# LoraWAN_Node.net
KiCad netlist of a schematic drawn in Altium Designer
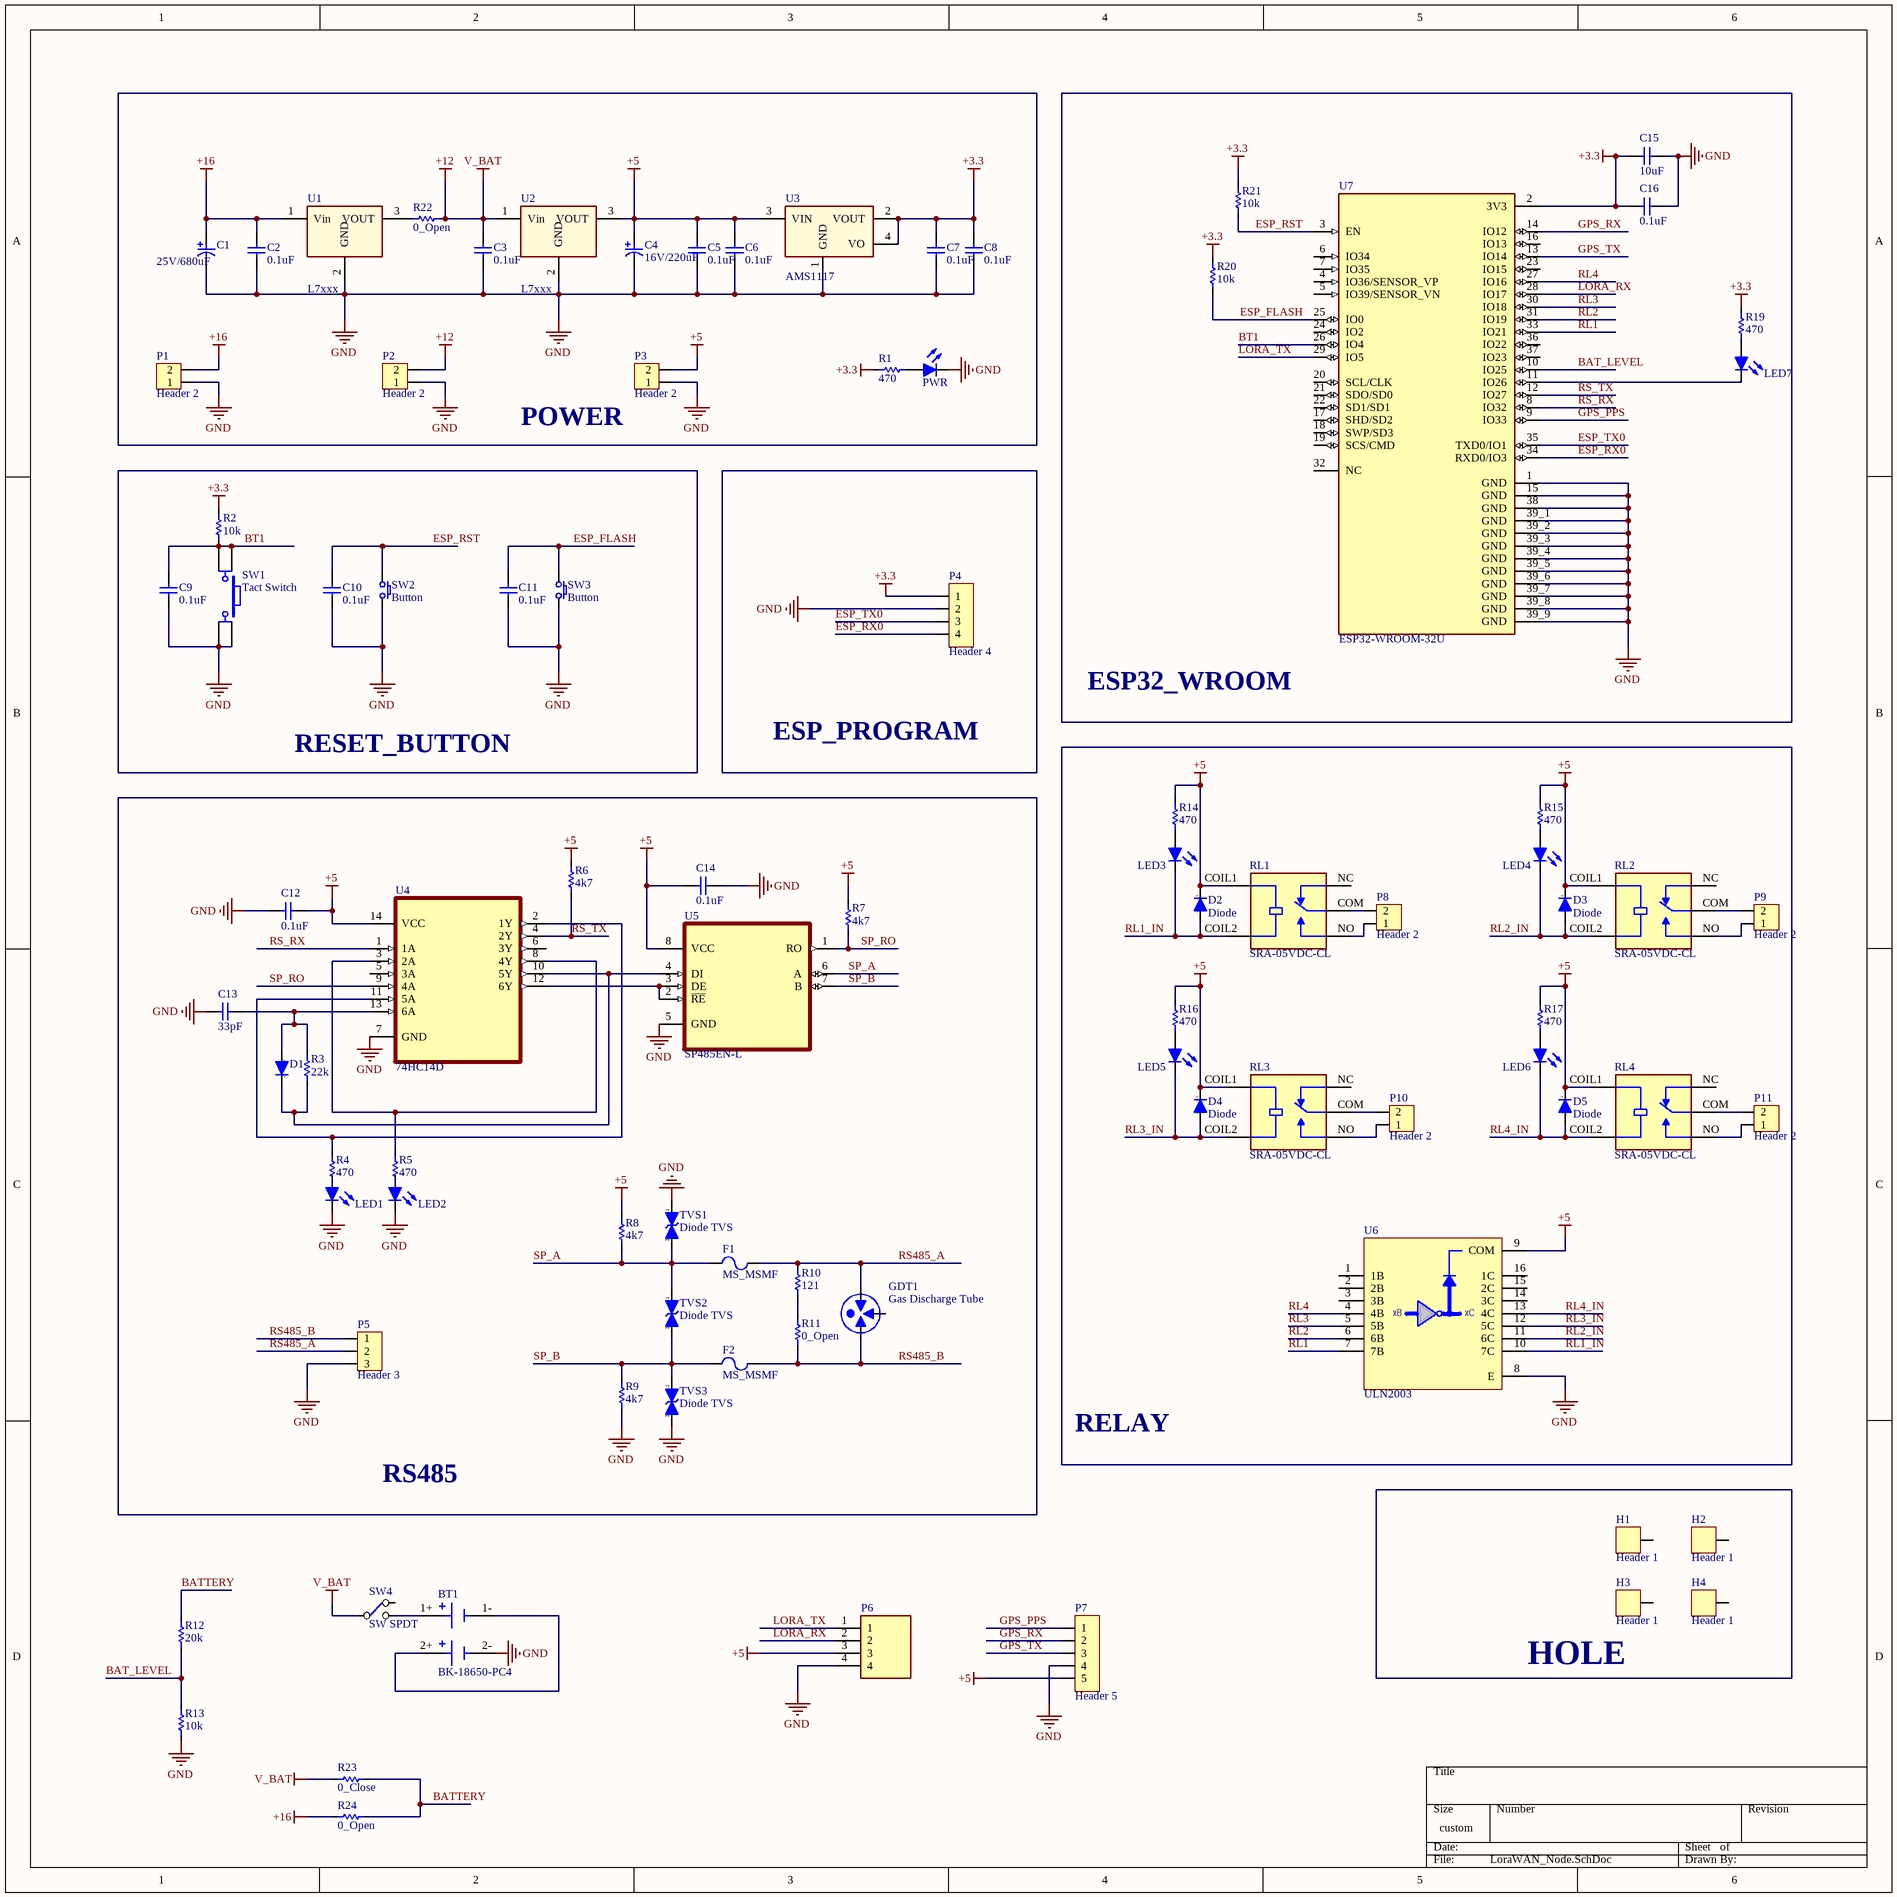
[diagram p0: LoraWAN_Node.SchDoc]

(export (version "E")
  (design (tool "Eeschema 10.0.6"))
  (components
    (comp (ref "BT1")
      (value "BK-18650-PC4")
      (footprint "BAT_BK-18650-PC4")
      (description "Battery Holder (Open) 18650 2 Cell PC Pin")
      (libsource (lib "BK-18650-PC4") (part "BK-18650-PC4"))
    )
    (comp (ref "C1")
      (value "25V/680uF")
      (footprint "C SMD ALU (G)")
      (description "Capacitor pol")
      (libsource (lib "BKIT4U_LIB_NEW") (part "Capacitor"))
    )
    (comp (ref "C2")
      (value "0.1uF")
      (footprint "C 0603 (1608)")
      (description "Capacitor non-pol")
      (libsource (lib "BKIT4U_LIB_NEW") (part "Capacitor NP"))
    )
    (comp (ref "C3")
      (value "0.1uF")
      (footprint "C 0603 (1608)")
      (description "Capacitor non-pol")
      (libsource (lib "BKIT4U_LIB_NEW") (part "Capacitor NP"))
    )
    (comp (ref "C4")
      (value "16V/220uF")
      (footprint "C SMD ALU (D8)")
      (description "Capacitor pol")
      (libsource (lib "BKIT4U_LIB_NEW") (part "Capacitor"))
    )
    (comp (ref "C5")
      (value "0.1uF")
      (footprint "C 0603 (1608)")
      (description "Capacitor non-pol")
      (libsource (lib "BKIT4U_LIB_NEW") (part "Capacitor NP"))
    )
    (comp (ref "C6")
      (value "0.1uF")
      (footprint "C 0603 (1608)")
      (description "Capacitor non-pol")
      (libsource (lib "BKIT4U_LIB_NEW") (part "Capacitor NP"))
    )
    (comp (ref "C7")
      (value "0.1uF")
      (footprint "C 0603 (1608)")
      (description "Capacitor non-pol")
      (libsource (lib "BKIT4U_LIB_NEW") (part "Capacitor NP"))
    )
    (comp (ref "C8")
      (value "0.1uF")
      (footprint "C 0603 (1608)")
      (description "Capacitor non-pol")
      (libsource (lib "BKIT4U_LIB_NEW") (part "Capacitor NP"))
    )
    (comp (ref "C9")
      (value "0.1uF")
      (footprint "C 0603 (1608)")
      (description "Capacitor non-pol")
      (libsource (lib "BKIT4U_LIB_NEW") (part "Capacitor NP"))
    )
    (comp (ref "C10")
      (value "0.1uF")
      (footprint "C 0603 (1608)")
      (description "Capacitor non-pol")
      (libsource (lib "BKIT4U_LIB_NEW") (part "Capacitor NP"))
    )
    (comp (ref "C11")
      (value "0.1uF")
      (footprint "C 0603 (1608)")
      (description "Capacitor non-pol")
      (libsource (lib "BKIT4U_LIB_NEW") (part "Capacitor NP"))
    )
    (comp (ref "C12")
      (value "0.1uF")
      (footprint "C 0603 (1608)")
      (description "Capacitor non-pol")
      (libsource (lib "BKIT4U_LIB_NEW") (part "Capacitor NP"))
    )
    (comp (ref "C13")
      (value "33pF")
      (footprint "C 0603 (1608)")
      (description "Capacitor non-pol")
      (libsource (lib "BKIT4U_LIB_NEW") (part "Capacitor NP"))
    )
    (comp (ref "C14")
      (value "0.1uF")
      (footprint "C 0603 (1608)")
      (description "Capacitor non-pol")
      (libsource (lib "BKIT4U_LIB_NEW") (part "Capacitor NP"))
    )
    (comp (ref "C15")
      (value "10uF")
      (footprint "C 0603 (1608)")
      (description "Capacitor non-pol")
      (libsource (lib "BKIT4U_LIB_NEW") (part "Capacitor NP"))
    )
    (comp (ref "C16")
      (value "0.1uF")
      (footprint "C 0603 (1608)")
      (description "Capacitor non-pol")
      (libsource (lib "BKIT4U_LIB_NEW") (part "Capacitor NP"))
    )
    (comp (ref "D1")
      (value "Diode")
      (footprint "DO-214AC (SMA)")
      (description "Default Diode")
      (fields (field (name "PUBLISHER") "Altium Limited"))
      (libsource (lib "BKIT4U_LIB_NEW") (part "Diode"))
    )
    (comp (ref "D2")
      (value "Diode")
      (footprint "DO-214AC (SMA)")
      (description "Default Diode")
      (fields (field (name "PUBLISHER") "Altium Limited"))
      (libsource (lib "BKIT4U_LIB_NEW") (part "Diode"))
    )
    (comp (ref "D3")
      (value "Diode")
      (footprint "DO-214AC (SMA)")
      (description "Default Diode")
      (fields (field (name "PUBLISHER") "Altium Limited"))
      (libsource (lib "BKIT4U_LIB_NEW") (part "Diode"))
    )
    (comp (ref "D4")
      (value "Diode")
      (footprint "DO-214AC (SMA)")
      (description "Default Diode")
      (fields (field (name "PUBLISHER") "Altium Limited"))
      (libsource (lib "BKIT4U_LIB_NEW") (part "Diode"))
    )
    (comp (ref "D5")
      (value "Diode")
      (footprint "DO-214AC (SMA)")
      (description "Default Diode")
      (fields (field (name "PUBLISHER") "Altium Limited"))
      (libsource (lib "BKIT4U_LIB_NEW") (part "Diode"))
    )
    (comp (ref "F1")
      (value "MS_MSMF")
      (footprint "Fuse 1812P050")
      (description "Fuse")
      (libsource (lib "BKIT4U_LIB_NEW") (part "Fuse"))
    )
    (comp (ref "F2")
      (value "MS_MSMF")
      (footprint "Fuse 1812P050")
      (description "Fuse")
      (libsource (lib "BKIT4U_LIB_NEW") (part "Fuse"))
    )
    (comp (ref "GDT1")
      (value "Gas Discharge Tube")
      (footprint "CAPC4532X110N")
      (libsource (lib "BKIT4U_LIB_NEW") (part "Gas Discharge Tube"))
    )
    (comp (ref "H1")
      (value "Header 1")
      (footprint "M3")
      (description "Header, 1-Pin")
      (fields (field (name "PUBLISHER") "Altium Limited"))
      (libsource (lib "BKIT4U_LIB_NEW") (part "Header 1"))
    )
    (comp (ref "H2")
      (value "Header 1")
      (footprint "M3")
      (description "Header, 1-Pin")
      (fields (field (name "PUBLISHER") "Altium Limited"))
      (libsource (lib "BKIT4U_LIB_NEW") (part "Header 1"))
    )
    (comp (ref "H3")
      (value "Header 1")
      (footprint "M3")
      (description "Header, 1-Pin")
      (fields (field (name "PUBLISHER") "Altium Limited"))
      (libsource (lib "BKIT4U_LIB_NEW") (part "Header 1"))
    )
    (comp (ref "H4")
      (value "Header 1")
      (footprint "M3")
      (description "Header, 1-Pin")
      (fields (field (name "PUBLISHER") "Altium Limited"))
      (libsource (lib "BKIT4U_LIB_NEW") (part "Header 1"))
    )
    (comp (ref "LED1")
      (value "Led")
      (footprint "Led SMD 0805")
      (description "Typical LED")
      (libsource (lib "BKIT4U_LIB_NEW") (part "Led"))
    )
    (comp (ref "LED2")
      (value "Led")
      (footprint "Led SMD 0805")
      (description "Typical LED")
      (libsource (lib "BKIT4U_LIB_NEW") (part "Led"))
    )
    (comp (ref "LED3")
      (value "Led")
      (footprint "Led SMD 0805")
      (description "Typical LED")
      (libsource (lib "BKIT4U_LIB_NEW") (part "Led"))
    )
    (comp (ref "LED4")
      (value "Led")
      (footprint "Led SMD 0805")
      (description "Typical LED")
      (libsource (lib "BKIT4U_LIB_NEW") (part "Led"))
    )
    (comp (ref "LED5")
      (value "Led")
      (footprint "Led SMD 0805")
      (description "Typical LED")
      (libsource (lib "BKIT4U_LIB_NEW") (part "Led"))
    )
    (comp (ref "LED6")
      (value "Led")
      (footprint "Led SMD 0805")
      (description "Typical LED")
      (libsource (lib "BKIT4U_LIB_NEW") (part "Led"))
    )
    (comp (ref "LED7")
      (value "Led")
      (footprint "Led SMD 0805")
      (description "Typical LED")
      (libsource (lib "BKIT4U_LIB_NEW") (part "Led"))
    )
    (comp (ref "P1")
      (value "Header 2")
      (footprint "XH2.54-2P")
      (description "Header, 2-Pin")
      (fields (field (name "PUBLISHER") "Altium Limited"))
      (libsource (lib "BKIT4U_LIB_NEW") (part "Header 2"))
    )
    (comp (ref "P2")
      (value "Header 2")
      (footprint "HDR Domino 2 - 5MM")
      (description "Header, 2-Pin")
      (fields (field (name "PUBLISHER") "Altium Limited"))
      (libsource (lib "BKIT4U_LIB_NEW") (part "Header 2"))
    )
    (comp (ref "P3")
      (value "Header 2")
      (footprint "HDR Domino 2 - 5MM")
      (description "Header, 2-Pin")
      (fields (field (name "PUBLISHER") "Altium Limited"))
      (libsource (lib "BKIT4U_LIB_NEW") (part "Header 2"))
    )
    (comp (ref "P4")
      (value "Header 4")
      (footprint "Header 4")
      (description "Header, 4-Pin")
      (libsource (lib "BKIT4U_LIB_NEW") (part "Header 4"))
    )
    (comp (ref "P5")
      (value "Header 3")
      (footprint "HDR Domino 3 - 5MM")
      (description "Header, 3-Pin")
      (libsource (lib "BKIT4U_LIB_NEW") (part "Header 3"))
    )
    (comp (ref "P6")
      (value "110990030")
      (footprint "SEEED_110990030")
      (fields (field (name "MF") "Seeed Technology"))
      (libsource (lib "110990030") (part "110990030"))
    )
    (comp (ref "P7")
      (value "Header 5")
      (footprint "Header 5")
      (description "Header, 5-Pin")
      (fields (field (name "PUBLISHER") "Altium Limited"))
      (libsource (lib "BKIT4U_LIB_NEW") (part "Header 5"))
    )
    (comp (ref "P8")
      (value "Header 2")
      (footprint "HDR Domino 2 - 5MM")
      (description "Header, 2-Pin")
      (fields (field (name "PUBLISHER") "Altium Limited"))
      (libsource (lib "") (part "Header 2_1"))
    )
    (comp (ref "P9")
      (value "Header 2")
      (footprint "HDR Domino 2 - 5MM")
      (description "Header, 2-Pin")
      (fields (field (name "PUBLISHER") "Altium Limited"))
      (libsource (lib "") (part "Header 2_1"))
    )
    (comp (ref "P10")
      (value "Header 2")
      (footprint "HDR Domino 2 - 5MM")
      (description "Header, 2-Pin")
      (fields (field (name "PUBLISHER") "Altium Limited"))
      (libsource (lib "") (part "Header 2_1"))
    )
    (comp (ref "P11")
      (value "Header 2")
      (footprint "HDR Domino 2 - 5MM")
      (description "Header, 2-Pin")
      (fields (field (name "PUBLISHER") "Altium Limited"))
      (libsource (lib "") (part "Header 2_1"))
    )
    (comp (ref "PWR")
      (value "Led")
      (footprint "Led SMD 0805")
      (description "Typical LED")
      (libsource (lib "BKIT4U_LIB_NEW") (part "Led"))
    )
    (comp (ref "R1")
      (value "470")
      (footprint "R 0603 (1608)")
      (description "Resistor")
      (fields (field (name "PUBLISHER") "Altium Limited"))
      (libsource (lib "BKIT4U_LIB_NEW") (part "Resistor"))
    )
    (comp (ref "R2")
      (value "10k")
      (footprint "R 0603 (1608)")
      (description "Resistor")
      (fields (field (name "PUBLISHER") "Altium Limited"))
      (libsource (lib "BKIT4U_LIB_NEW") (part "Resistor"))
    )
    (comp (ref "R3")
      (value "22k")
      (footprint "R 0603 (1608)")
      (description "Resistor")
      (fields (field (name "PUBLISHER") "Altium Limited"))
      (libsource (lib "BKIT4U_LIB_NEW") (part "Resistor"))
    )
    (comp (ref "R4")
      (value "470")
      (footprint "R 0603 (1608)")
      (description "Resistor")
      (fields (field (name "PUBLISHER") "Altium Limited"))
      (libsource (lib "BKIT4U_LIB_NEW") (part "Resistor"))
    )
    (comp (ref "R5")
      (value "470")
      (footprint "R 0603 (1608)")
      (description "Resistor")
      (fields (field (name "PUBLISHER") "Altium Limited"))
      (libsource (lib "BKIT4U_LIB_NEW") (part "Resistor"))
    )
    (comp (ref "R6")
      (value "4k7")
      (footprint "R 0603 (1608)")
      (description "Resistor")
      (fields (field (name "PUBLISHER") "Altium Limited"))
      (libsource (lib "BKIT4U_LIB_NEW") (part "Resistor"))
    )
    (comp (ref "R7")
      (value "4k7")
      (footprint "R 0603 (1608)")
      (description "Resistor")
      (fields (field (name "PUBLISHER") "Altium Limited"))
      (libsource (lib "BKIT4U_LIB_NEW") (part "Resistor"))
    )
    (comp (ref "R8")
      (value "4k7")
      (footprint "R 0603 (1608)")
      (description "Resistor")
      (fields (field (name "PUBLISHER") "Altium Limited"))
      (libsource (lib "BKIT4U_LIB_NEW") (part "Resistor"))
    )
    (comp (ref "R9")
      (value "4k7")
      (footprint "R 0603 (1608)")
      (description "Resistor")
      (fields (field (name "PUBLISHER") "Altium Limited"))
      (libsource (lib "BKIT4U_LIB_NEW") (part "Resistor"))
    )
    (comp (ref "R10")
      (value "121")
      (footprint "R 0603 (1608)")
      (description "Resistor")
      (fields (field (name "PUBLISHER") "Altium Limited"))
      (libsource (lib "BKIT4U_LIB_NEW") (part "Resistor"))
    )
    (comp (ref "R11")
      (value "0_Open")
      (footprint "R 0603 (1608)")
      (description "Resistor")
      (fields (field (name "PUBLISHER") "Altium Limited"))
      (libsource (lib "BKIT4U_LIB_NEW") (part "Resistor"))
    )
    (comp (ref "R12")
      (value "20k")
      (footprint "R 0603 (1608)")
      (description "Resistor")
      (fields (field (name "PUBLISHER") "Altium Limited"))
      (libsource (lib "BKIT4U_LIB_NEW") (part "Resistor"))
    )
    (comp (ref "R13")
      (value "10k")
      (footprint "R 0603 (1608)")
      (description "Resistor")
      (fields (field (name "PUBLISHER") "Altium Limited"))
      (libsource (lib "BKIT4U_LIB_NEW") (part "Resistor"))
    )
    (comp (ref "R14")
      (value "470")
      (footprint "R 0603 (1608)")
      (description "Resistor")
      (fields (field (name "PUBLISHER") "Altium Limited"))
      (libsource (lib "BKIT4U_LIB_NEW") (part "Resistor"))
    )
    (comp (ref "R15")
      (value "470")
      (footprint "R 0603 (1608)")
      (description "Resistor")
      (fields (field (name "PUBLISHER") "Altium Limited"))
      (libsource (lib "BKIT4U_LIB_NEW") (part "Resistor"))
    )
    (comp (ref "R16")
      (value "470")
      (footprint "R 0603 (1608)")
      (description "Resistor")
      (fields (field (name "PUBLISHER") "Altium Limited"))
      (libsource (lib "BKIT4U_LIB_NEW") (part "Resistor"))
    )
    (comp (ref "R17")
      (value "470")
      (footprint "R 0603 (1608)")
      (description "Resistor")
      (fields (field (name "PUBLISHER") "Altium Limited"))
      (libsource (lib "BKIT4U_LIB_NEW") (part "Resistor"))
    )
    (comp (ref "R19")
      (value "470")
      (footprint "R 0603 (1608)")
      (description "Resistor")
      (fields (field (name "PUBLISHER") "Altium Limited"))
      (libsource (lib "BKIT4U_LIB_NEW") (part "Resistor"))
    )
    (comp (ref "R20")
      (value "10k")
      (footprint "R 0603 (1608)")
      (description "Resistor")
      (fields (field (name "PUBLISHER") "Altium Limited"))
      (libsource (lib "BKIT4U_LIB_NEW") (part "Resistor"))
    )
    (comp (ref "R21")
      (value "10k")
      (footprint "R 0603 (1608)")
      (description "Resistor")
      (fields (field (name "PUBLISHER") "Altium Limited"))
      (libsource (lib "BKIT4U_LIB_NEW") (part "Resistor"))
    )
    (comp (ref "R22")
      (value "0_Open")
      (footprint "R 0603 (1608)")
      (description "Resistor")
      (fields (field (name "PUBLISHER") "Altium Limited"))
      (libsource (lib "BKIT4U_LIB_NEW") (part "Resistor"))
    )
    (comp (ref "R23")
      (value "0_Close")
      (footprint "R 0603 (1608)")
      (description "Resistor")
      (fields (field (name "PUBLISHER") "Altium Limited"))
      (libsource (lib "BKIT4U_LIB_NEW") (part "Resistor"))
    )
    (comp (ref "R24")
      (value "0_Open")
      (footprint "R 0603 (1608)")
      (description "Resistor")
      (fields (field (name "PUBLISHER") "Altium Limited"))
      (libsource (lib "BKIT4U_LIB_NEW") (part "Resistor"))
    )
    (comp (ref "RL1")
      (value "SRA-05VDC-CL")
      (footprint "RELAY_SRA-05VDC-CL")
      (fields (field (name "MF") "Songle Relay"))
      (libsource (lib "SRA-05VDC-CL") (part "SRA-05VDC-CL"))
    )
    (comp (ref "RL2")
      (value "SRA-05VDC-CL")
      (footprint "RELAY_SRA-05VDC-CL")
      (fields (field (name "MF") "Songle Relay"))
      (libsource (lib "SRA-05VDC-CL") (part "SRA-05VDC-CL"))
    )
    (comp (ref "RL3")
      (value "SRA-05VDC-CL")
      (footprint "RELAY_SRA-05VDC-CL")
      (fields (field (name "MF") "Songle Relay"))
      (libsource (lib "SRA-05VDC-CL") (part "SRA-05VDC-CL"))
    )
    (comp (ref "RL4")
      (value "SRA-05VDC-CL")
      (footprint "RELAY_SRA-05VDC-CL")
      (fields (field (name "MF") "Songle Relay"))
      (libsource (lib "SRA-05VDC-CL") (part "SRA-05VDC-CL"))
    )
    (comp (ref "SW1")
      (value "Tact Switch")
      (footprint "SW/4/DIP/SMALL")
      (description "Tact switch 4 pin")
      (libsource (lib "BKIT4U_LIB_NEW") (part "SW SPST-4"))
    )
    (comp (ref "SW2")
      (value "Button")
      (footprint "SW/2/SMD")
      (description "Tact switch 2 pin")
      (libsource (lib "BKIT4U_LIB_NEW") (part "SW SPST"))
    )
    (comp (ref "SW3")
      (value "Button")
      (footprint "SW/2/SMD")
      (description "Tact switch 2 pin")
      (libsource (lib "BKIT4U_LIB_NEW") (part "SW SPST"))
    )
    (comp (ref "SW4")
      (value "SW SPDT")
      (footprint "SW/3/SPDT/SS12D10")
      (libsource (lib "chipfc_altium_libs") (part "SW SPDT"))
    )
    (comp (ref "TVS1")
      (value "Diode TVS")
      (footprint "DO-214AA (SMB)")
      (description "Bi-directional TVS Diode")
      (fields (field (name "PUBLISHER") "Altium Limited"))
      (libsource (lib "BKIT4U_LIB_NEW") (part "Diode TVS Bi-Dir"))
    )
    (comp (ref "TVS2")
      (value "Diode TVS")
      (footprint "DO-214AA (SMB)")
      (description "Bi-directional TVS Diode")
      (fields (field (name "PUBLISHER") "Altium Limited"))
      (libsource (lib "BKIT4U_LIB_NEW") (part "Diode TVS Bi-Dir"))
    )
    (comp (ref "TVS3")
      (value "Diode TVS")
      (footprint "DO-214AA (SMB)")
      (description "Bi-directional TVS Diode")
      (fields (field (name "PUBLISHER") "Altium Limited"))
      (libsource (lib "BKIT4U_LIB_NEW") (part "Diode TVS Bi-Dir"))
    )
    (comp (ref "U1")
      (value "L7xxx")
      (footprint "TO-263 (D2PAK)")
      (description "LDO Fixed Voltage regulator")
      (libsource (lib "BKIT4U_LIB_NEW") (part "L7xxx"))
    )
    (comp (ref "U2")
      (value "L7xxx")
      (footprint "TO-263 (D2PAK)")
      (description "LDO Fixed Voltage regulator")
      (libsource (lib "BKIT4U_LIB_NEW") (part "L7xxx"))
    )
    (comp (ref "U3")
      (value "AMS1117")
      (footprint "SOT-223")
      (description "1A LDO Voltage Regulator, ADJ or fixed 1.5/1.8/2.5/2.85/3.3/5V")
      (libsource (lib "BKIT4U_LIB_NEW") (part "AMS1117"))
    )
    (comp (ref "U4")
      (value "74HC14D")
      (footprint "SOIC127P600X175-14N")
      (description "Inverter IC 6 Channel Schmitt Trigger 14-SOIC")
      (fields (field (name "MF") "Toshiba"))
      (libsource (lib "74HC14D") (part "74HC14D"))
    )
    (comp (ref "U5")
      (value "SP485EN-L")
      (footprint "SOIC-8")
      (description "SP485 Series 5 Mbps 5 V Low Power Half Duplex RS-485 Transceiver - NSOIC-8")
      (fields (field (name "MF") "MaxLinear, Inc."))
      (libsource (lib "SP485EN-L") (part "SP485EN-L"))
    )
    (comp (ref "U6")
      (value "ULN2003")
      (footprint "SOIC-16")
      (description "High-voltage, high-current Darlington transistor arrays")
      (libsource (lib "BKIT4U_LIB_NEW") (part "ULN2003"))
    )
    (comp (ref "U7")
      (value "ESP32-WROOM-32U")
      (footprint "XCVR_ESP32-WROOM-32U")
      (fields (field (name "MF") "Espressif Systems"))
      (libsource (lib "ESP32-WROOM-32U") (part "ESP32-WROOM-32U"))
    )
  )
  (nets
    (net (code "1") (name "+3.3") (class "Default")
      (node (ref "C15") (pin "1") (pinfunction "1_1") (pintype "passive"))
      (node (ref "C16") (pin "1") (pinfunction "1_1") (pintype "passive"))
      (node (ref "C7") (pin "1") (pinfunction "1_1") (pintype "passive"))
      (node (ref "C8") (pin "1") (pinfunction "1_1") (pintype "passive"))
      (node (ref "P4") (pin "1") (pinfunction "1_1") (pintype "passive"))
      (node (ref "R1") (pin "2") (pinfunction "2_2") (pintype "passive"))
      (node (ref "R19") (pin "2") (pinfunction "2_2") (pintype "passive"))
      (node (ref "R2") (pin "2") (pinfunction "2_2") (pintype "passive"))
      (node (ref "R20") (pin "2") (pinfunction "2_2") (pintype "passive"))
      (node (ref "R21") (pin "2") (pinfunction "2_2") (pintype "passive"))
      (node (ref "U3") (pin "2") (pinfunction "VOUT_2") (pintype "passive"))
      (node (ref "U3") (pin "4") (pinfunction "VO_4") (pintype "passive"))
      (node (ref "U7") (pin "2") (pinfunction "3V3_2") (pintype "power_in"))
    )
    (net (code "2") (name "+5") (class "Default")
      (node (ref "C12") (pin "2") (pinfunction "2_2") (pintype "passive"))
      (node (ref "C14") (pin "1") (pinfunction "1_1") (pintype "passive"))
      (node (ref "C4") (pin "1") (pinfunction "1_1") (pintype "passive"))
      (node (ref "C5") (pin "1") (pinfunction "1_1") (pintype "passive"))
      (node (ref "C6") (pin "1") (pinfunction "1_1") (pintype "passive"))
      (node (ref "D2") (pin "1") (pinfunction "Cathode_1") (pintype "passive"))
      (node (ref "D3") (pin "1") (pinfunction "Cathode_1") (pintype "passive"))
      (node (ref "D4") (pin "1") (pinfunction "Cathode_1") (pintype "passive"))
      (node (ref "D5") (pin "1") (pinfunction "Cathode_1") (pintype "passive"))
      (node (ref "P3") (pin "2") (pinfunction "2_2") (pintype "passive"))
      (node (ref "P6") (pin "3") (pinfunction "3_3") (pintype "passive"))
      (node (ref "P7") (pin "5") (pinfunction "5_5") (pintype "passive"))
      (node (ref "R14") (pin "2") (pinfunction "2_2") (pintype "passive"))
      (node (ref "R15") (pin "2") (pinfunction "2_2") (pintype "passive"))
      (node (ref "R16") (pin "2") (pinfunction "2_2") (pintype "passive"))
      (node (ref "R17") (pin "2") (pinfunction "2_2") (pintype "passive"))
      (node (ref "R6") (pin "2") (pinfunction "2_2") (pintype "passive"))
      (node (ref "R7") (pin "2") (pinfunction "2_2") (pintype "passive"))
      (node (ref "R8") (pin "2") (pinfunction "2_2") (pintype "passive"))
      (node (ref "RL1") (pin "COIL1") (pinfunction "COIL1_COIL1") (pintype "passive"))
      (node (ref "RL2") (pin "COIL1") (pinfunction "COIL1_COIL1") (pintype "passive"))
      (node (ref "RL3") (pin "COIL1") (pinfunction "COIL1_COIL1") (pintype "passive"))
      (node (ref "RL4") (pin "COIL1") (pinfunction "COIL1_COIL1") (pintype "passive"))
      (node (ref "U2") (pin "3") (pinfunction "VOUT_3") (pintype "passive"))
      (node (ref "U3") (pin "3") (pinfunction "VIN_3") (pintype "power_in"))
      (node (ref "U4") (pin "14") (pinfunction "VCC_14") (pintype "power_in"))
      (node (ref "U5") (pin "8") (pinfunction "VCC_8") (pintype "power_in"))
      (node (ref "U6") (pin "9") (pinfunction "COM_9") (pintype "passive"))
    )
    (net (code "3") (name "+12") (class "Default")
      (node (ref "C3") (pin "1") (pinfunction "1_1") (pintype "passive"))
      (node (ref "P2") (pin "2") (pinfunction "2_2") (pintype "passive"))
      (node (ref "R22") (pin "1") (pinfunction "1_1") (pintype "passive"))
      (node (ref "R23") (pin "2") (pinfunction "2_2") (pintype "passive"))
      (node (ref "SW4") (pin "2") (pinfunction "COMMON1_2") (pintype "passive"))
      (node (ref "U2") (pin "1") (pinfunction "Vin_1") (pintype "power_in"))
    )
    (net (code "4") (name "+16") (class "Default")
      (node (ref "C1") (pin "1") (pinfunction "1_1") (pintype "passive"))
      (node (ref "C2") (pin "1") (pinfunction "1_1") (pintype "passive"))
      (node (ref "P1") (pin "2") (pinfunction "2_2") (pintype "passive"))
      (node (ref "R24") (pin "2") (pinfunction "2_2") (pintype "passive"))
      (node (ref "U1") (pin "1") (pinfunction "Vin_1") (pintype "power_in"))
    )
    (net (code "5") (name "/BATTERY") (class "Default")
      (node (ref "R12") (pin "2") (pinfunction "2_2") (pintype "passive"))
      (node (ref "R23") (pin "1") (pinfunction "1_1") (pintype "passive"))
      (node (ref "R24") (pin "1") (pinfunction "1_1") (pintype "passive"))
    )
    (net (code "6") (name "/BAT_LEVEL") (class "Default")
      (node (ref "R12") (pin "1") (pinfunction "1_1") (pintype "passive"))
      (node (ref "R13") (pin "2") (pinfunction "2_2") (pintype "passive"))
      (node (ref "U7") (pin "10") (pinfunction "IO25_10") (pintype "bidirectional"))
    )
    (net (code "7") (name "/BT1") (class "Default")
      (node (ref "C9") (pin "1") (pinfunction "1_1") (pintype "passive"))
      (node (ref "R2") (pin "1") (pinfunction "1_1") (pintype "passive"))
      (node (ref "SW1") (pin "1") (pinfunction "1_1") (pintype "passive"))
      (node (ref "SW1") (pin "4") (pinfunction "2_4") (pintype "passive"))
      (node (ref "U7") (pin "26") (pinfunction "IO4_26") (pintype "bidirectional"))
    )
    (net (code "8") (name "/ESP_FLASH") (class "Default")
      (node (ref "C11") (pin "1") (pinfunction "1_1") (pintype "passive"))
      (node (ref "R20") (pin "1") (pinfunction "1_1") (pintype "passive"))
      (node (ref "SW3") (pin "1") (pinfunction "1_1") (pintype "passive"))
      (node (ref "U7") (pin "25") (pinfunction "IO0_25") (pintype "bidirectional"))
    )
    (net (code "9") (name "/ESP_RST") (class "Default")
      (node (ref "C10") (pin "1") (pinfunction "1_1") (pintype "passive"))
      (node (ref "R21") (pin "1") (pinfunction "1_1") (pintype "passive"))
      (node (ref "SW2") (pin "1") (pinfunction "1_1") (pintype "passive"))
      (node (ref "U7") (pin "3") (pinfunction "EN_3") (pintype "input"))
    )
    (net (code "10") (name "/ESP_RX0") (class "Default")
      (node (ref "P4") (pin "4") (pinfunction "4_4") (pintype "passive"))
      (node (ref "U7") (pin "34") (pinfunction "RXD0/IO3_34") (pintype "bidirectional"))
    )
    (net (code "11") (name "/ESP_TX0") (class "Default")
      (node (ref "P4") (pin "3") (pinfunction "3_3") (pintype "passive"))
      (node (ref "U7") (pin "35") (pinfunction "TXD0/IO1_35") (pintype "bidirectional"))
    )
    (net (code "12") (name "/GPS_PPS") (class "Default")
      (node (ref "P7") (pin "1") (pinfunction "1_1") (pintype "passive"))
      (node (ref "U7") (pin "9") (pinfunction "IO33_9") (pintype "bidirectional"))
    )
    (net (code "13") (name "/GPS_RX") (class "Default")
      (node (ref "P7") (pin "2") (pinfunction "2_2") (pintype "passive"))
      (node (ref "U7") (pin "14") (pinfunction "IO12_14") (pintype "bidirectional"))
    )
    (net (code "14") (name "/GPS_TX") (class "Default")
      (node (ref "P7") (pin "3") (pinfunction "3_3") (pintype "passive"))
      (node (ref "U7") (pin "13") (pinfunction "IO14_13") (pintype "bidirectional"))
    )
    (net (code "15") (name "/LORA_RX") (class "Default")
      (node (ref "P6") (pin "2") (pinfunction "2_2") (pintype "passive"))
      (node (ref "U7") (pin "28") (pinfunction "IO17_28") (pintype "bidirectional"))
    )
    (net (code "16") (name "/LORA_TX") (class "Default")
      (node (ref "P6") (pin "1") (pinfunction "1_1") (pintype "passive"))
      (node (ref "U7") (pin "29") (pinfunction "IO5_29") (pintype "bidirectional"))
    )
    (net (code "17") (name "/RL1") (class "Default")
      (node (ref "U6") (pin "7") (pinfunction "7B_7") (pintype "passive"))
      (node (ref "U7") (pin "33") (pinfunction "IO21_33") (pintype "bidirectional"))
    )
    (net (code "18") (name "/RL1_IN") (class "Default")
      (node (ref "D2") (pin "2") (pinfunction "Anode_2") (pintype "passive"))
      (node (ref "LED3") (pin "1") (pinfunction "K_1") (pintype "passive"))
      (node (ref "RL1") (pin "COIL2") (pinfunction "COIL2_COIL2") (pintype "passive"))
      (node (ref "U6") (pin "10") (pinfunction "7C_10") (pintype "passive"))
    )
    (net (code "19") (name "/RL2") (class "Default")
      (node (ref "U6") (pin "6") (pinfunction "6B_6") (pintype "passive"))
      (node (ref "U7") (pin "31") (pinfunction "IO19_31") (pintype "bidirectional"))
    )
    (net (code "20") (name "/RL2_IN") (class "Default")
      (node (ref "D3") (pin "2") (pinfunction "Anode_2") (pintype "passive"))
      (node (ref "LED4") (pin "1") (pinfunction "K_1") (pintype "passive"))
      (node (ref "RL2") (pin "COIL2") (pinfunction "COIL2_COIL2") (pintype "passive"))
      (node (ref "U6") (pin "11") (pinfunction "6C_11") (pintype "passive"))
    )
    (net (code "21") (name "/RL3") (class "Default")
      (node (ref "U6") (pin "5") (pinfunction "5B_5") (pintype "passive"))
      (node (ref "U7") (pin "30") (pinfunction "IO18_30") (pintype "bidirectional"))
    )
    (net (code "22") (name "/RL3_IN") (class "Default")
      (node (ref "D4") (pin "2") (pinfunction "Anode_2") (pintype "passive"))
      (node (ref "LED5") (pin "1") (pinfunction "K_1") (pintype "passive"))
      (node (ref "RL3") (pin "COIL2") (pinfunction "COIL2_COIL2") (pintype "passive"))
      (node (ref "U6") (pin "12") (pinfunction "5C_12") (pintype "passive"))
    )
    (net (code "23") (name "/RL4") (class "Default")
      (node (ref "U6") (pin "4") (pinfunction "4B_4") (pintype "passive"))
      (node (ref "U7") (pin "27") (pinfunction "IO16_27") (pintype "bidirectional"))
    )
    (net (code "24") (name "/RL4_IN") (class "Default")
      (node (ref "D5") (pin "2") (pinfunction "Anode_2") (pintype "passive"))
      (node (ref "LED6") (pin "1") (pinfunction "K_1") (pintype "passive"))
      (node (ref "RL4") (pin "COIL2") (pinfunction "COIL2_COIL2") (pintype "passive"))
      (node (ref "U6") (pin "13") (pinfunction "4C_13") (pintype "passive"))
    )
    (net (code "25") (name "/RS485_A") (class "Default")
      (node (ref "F1") (pin "2") (pinfunction "2_2") (pintype "passive"))
      (node (ref "GDT1") (pin "1") (pinfunction "1_1") (pintype "passive"))
      (node (ref "P5") (pin "2") (pinfunction "2_2") (pintype "passive"))
      (node (ref "R10") (pin "1") (pinfunction "1_1") (pintype "passive"))
    )
    (net (code "26") (name "/RS485_B") (class "Default")
      (node (ref "F2") (pin "2") (pinfunction "2_2") (pintype "passive"))
      (node (ref "GDT1") (pin "2") (pinfunction "2_2") (pintype "passive"))
      (node (ref "P5") (pin "1") (pinfunction "1_1") (pintype "passive"))
      (node (ref "R11") (pin "2") (pinfunction "2_2") (pintype "passive"))
    )
    (net (code "27") (name "/RS_RX") (class "Default")
      (node (ref "U4") (pin "1") (pinfunction "1A_1") (pintype "input"))
      (node (ref "U7") (pin "8") (pinfunction "IO32_8") (pintype "bidirectional"))
    )
    (net (code "28") (name "/RS_TX") (class "Default")
      (node (ref "R6") (pin "1") (pinfunction "1_1") (pintype "passive"))
      (node (ref "U4") (pin "4") (pinfunction "2Y_4") (pintype "output"))
      (node (ref "U7") (pin "12") (pinfunction "IO27_12") (pintype "bidirectional"))
    )
    (net (code "29") (name "/SP_A") (class "Default")
      (node (ref "F1") (pin "1") (pinfunction "1_1") (pintype "passive"))
      (node (ref "R8") (pin "1") (pinfunction "1_1") (pintype "passive"))
      (node (ref "TVS1") (pin "2") (pinfunction "K_2") (pintype "passive"))
      (node (ref "TVS2") (pin "1") (pinfunction "A_1") (pintype "passive"))
      (node (ref "U5") (pin "6") (pinfunction "A_6") (pintype "bidirectional"))
    )
    (net (code "30") (name "/SP_B") (class "Default")
      (node (ref "F2") (pin "1") (pinfunction "1_1") (pintype "passive"))
      (node (ref "R9") (pin "2") (pinfunction "2_2") (pintype "passive"))
      (node (ref "TVS2") (pin "2") (pinfunction "K_2") (pintype "passive"))
      (node (ref "TVS3") (pin "1") (pinfunction "A_1") (pintype "passive"))
      (node (ref "U5") (pin "7") (pinfunction "B_7") (pintype "bidirectional"))
    )
    (net (code "31") (name "/SP_RO") (class "Default")
      (node (ref "R7") (pin "1") (pinfunction "1_1") (pintype "passive"))
      (node (ref "U4") (pin "9") (pinfunction "4A_9") (pintype "input"))
      (node (ref "U5") (pin "1") (pinfunction "RO_1") (pintype "output"))
    )
    (net (code "32") (name "GND") (class "Default")
      (node (ref "BT1") (pin "2-") (pinfunction "2-_2-") (pintype "passive"))
      (node (ref "C1") (pin "2") (pinfunction "2_2") (pintype "passive"))
      (node (ref "C10") (pin "2") (pinfunction "2_2") (pintype "passive"))
      (node (ref "C11") (pin "2") (pinfunction "2_2") (pintype "passive"))
      (node (ref "C12") (pin "1") (pinfunction "1_1") (pintype "passive"))
      (node (ref "C13") (pin "1") (pinfunction "1_1") (pintype "passive"))
      (node (ref "C14") (pin "2") (pinfunction "2_2") (pintype "passive"))
      (node (ref "C15") (pin "2") (pinfunction "2_2") (pintype "passive"))
      (node (ref "C16") (pin "2") (pinfunction "2_2") (pintype "passive"))
      (node (ref "C2") (pin "2") (pinfunction "2_2") (pintype "passive"))
      (node (ref "C3") (pin "2") (pinfunction "2_2") (pintype "passive"))
      (node (ref "C4") (pin "2") (pinfunction "2_2") (pintype "passive"))
      (node (ref "C5") (pin "2") (pinfunction "2_2") (pintype "passive"))
      (node (ref "C6") (pin "2") (pinfunction "2_2") (pintype "passive"))
      (node (ref "C7") (pin "2") (pinfunction "2_2") (pintype "passive"))
      (node (ref "C8") (pin "2") (pinfunction "2_2") (pintype "passive"))
      (node (ref "C9") (pin "2") (pinfunction "2_2") (pintype "passive"))
      (node (ref "LED1") (pin "1") (pinfunction "K_1") (pintype "passive"))
      (node (ref "LED2") (pin "1") (pinfunction "K_1") (pintype "passive"))
      (node (ref "P1") (pin "1") (pinfunction "1_1") (pintype "passive"))
      (node (ref "P2") (pin "1") (pinfunction "1_1") (pintype "passive"))
      (node (ref "P3") (pin "1") (pinfunction "1_1") (pintype "passive"))
      (node (ref "P4") (pin "2") (pinfunction "2_2") (pintype "passive"))
      (node (ref "P5") (pin "3") (pinfunction "3_3") (pintype "passive"))
      (node (ref "P6") (pin "4") (pinfunction "4_4") (pintype "passive"))
      (node (ref "P7") (pin "4") (pinfunction "4_4") (pintype "passive"))
      (node (ref "PWR") (pin "1") (pinfunction "K_1") (pintype "passive"))
      (node (ref "R13") (pin "1") (pinfunction "1_1") (pintype "passive"))
      (node (ref "R9") (pin "1") (pinfunction "1_1") (pintype "passive"))
      (node (ref "SW1") (pin "2") (pinfunction "2_2") (pintype "passive"))
      (node (ref "SW1") (pin "3") (pinfunction "1_3") (pintype "passive"))
      (node (ref "SW2") (pin "2") (pinfunction "2_2") (pintype "passive"))
      (node (ref "SW3") (pin "2") (pinfunction "2_2") (pintype "passive"))
      (node (ref "TVS1") (pin "1") (pinfunction "A_1") (pintype "passive"))
      (node (ref "TVS3") (pin "2") (pinfunction "K_2") (pintype "passive"))
      (node (ref "U1") (pin "2") (pinfunction "GND_2") (pintype "passive"))
      (node (ref "U2") (pin "2") (pinfunction "GND_2") (pintype "passive"))
      (node (ref "U3") (pin "1") (pinfunction "GND_1") (pintype "passive"))
      (node (ref "U4") (pin "7") (pinfunction "GND_7") (pintype "passive"))
      (node (ref "U5") (pin "5") (pinfunction "GND_5") (pintype "passive"))
      (node (ref "U6") (pin "8") (pinfunction "E_8") (pintype "passive"))
      (node (ref "U7") (pin "1") (pinfunction "GND_1") (pintype "power_in"))
      (node (ref "U7") (pin "15") (pinfunction "GND_15") (pintype "power_in"))
      (node (ref "U7") (pin "38") (pinfunction "GND_38") (pintype "power_in"))
      (node (ref "U7") (pin "39_1") (pinfunction "GND_39_1") (pintype "power_in"))
      (node (ref "U7") (pin "39_2") (pinfunction "GND_39_2") (pintype "power_in"))
      (node (ref "U7") (pin "39_3") (pinfunction "GND_39_3") (pintype "power_in"))
      (node (ref "U7") (pin "39_4") (pinfunction "GND_39_4") (pintype "power_in"))
      (node (ref "U7") (pin "39_5") (pinfunction "GND_39_5") (pintype "power_in"))
      (node (ref "U7") (pin "39_6") (pinfunction "GND_39_6") (pintype "power_in"))
      (node (ref "U7") (pin "39_7") (pinfunction "GND_39_7") (pintype "power_in"))
      (node (ref "U7") (pin "39_8") (pinfunction "GND_39_8") (pintype "power_in"))
      (node (ref "U7") (pin "39_9") (pinfunction "GND_39_9") (pintype "power_in"))
    )
    (net (code "33") (name "Net-(BT1-Pad1-)") (class "Default")
      (node (ref "BT1") (pin "1-") (pinfunction "1-_1-") (pintype "passive"))
      (node (ref "BT1") (pin "2+") (pinfunction "2+_2+") (pintype "passive"))
    )
    (net (code "34") (name "Net-(D1-Anode)") (class "Default")
      (node (ref "C13") (pin "2") (pinfunction "2_2") (pintype "passive"))
      (node (ref "D1") (pin "2") (pinfunction "Anode_2") (pintype "passive"))
      (node (ref "R3") (pin "2") (pinfunction "2_2") (pintype "passive"))
      (node (ref "U4") (pin "13") (pinfunction "6A_13") (pintype "input"))
    )
    (net (code "35") (name "Net-(D1-Cathode)") (class "Default")
      (node (ref "D1") (pin "1") (pinfunction "Cathode_1") (pintype "passive"))
      (node (ref "R3") (pin "1") (pinfunction "1_1") (pintype "passive"))
      (node (ref "U4") (pin "10") (pinfunction "5Y_10") (pintype "output"))
      (node (ref "U5") (pin "4") (pinfunction "DI_4") (pintype "input"))
    )
    (net (code "36") (name "Net-(LED1-A)") (class "Default")
      (node (ref "LED1") (pin "2") (pinfunction "A_2") (pintype "passive"))
      (node (ref "R4") (pin "1") (pinfunction "1_1") (pintype "passive"))
    )
    (net (code "37") (name "Net-(LED2-A)") (class "Default")
      (node (ref "LED2") (pin "2") (pinfunction "A_2") (pintype "passive"))
      (node (ref "R5") (pin "1") (pinfunction "1_1") (pintype "passive"))
    )
    (net (code "38") (name "Net-(LED3-A)") (class "Default")
      (node (ref "LED3") (pin "2") (pinfunction "A_2") (pintype "passive"))
      (node (ref "R14") (pin "1") (pinfunction "1_1") (pintype "passive"))
    )
    (net (code "39") (name "Net-(LED4-A)") (class "Default")
      (node (ref "LED4") (pin "2") (pinfunction "A_2") (pintype "passive"))
      (node (ref "R15") (pin "1") (pinfunction "1_1") (pintype "passive"))
    )
    (net (code "40") (name "Net-(LED5-A)") (class "Default")
      (node (ref "LED5") (pin "2") (pinfunction "A_2") (pintype "passive"))
      (node (ref "R16") (pin "1") (pinfunction "1_1") (pintype "passive"))
    )
    (net (code "41") (name "Net-(LED6-A)") (class "Default")
      (node (ref "LED6") (pin "2") (pinfunction "A_2") (pintype "passive"))
      (node (ref "R17") (pin "1") (pinfunction "1_1") (pintype "passive"))
    )
    (net (code "42") (name "Net-(LED7-A)") (class "Default")
      (node (ref "LED7") (pin "2") (pinfunction "A_2") (pintype "passive"))
      (node (ref "R19") (pin "1") (pinfunction "1_1") (pintype "passive"))
    )
    (net (code "43") (name "Net-(LED7-K)") (class "Default")
      (node (ref "LED7") (pin "1") (pinfunction "K_1") (pintype "passive"))
      (node (ref "U7") (pin "11") (pinfunction "IO26_11") (pintype "bidirectional"))
    )
    (net (code "44") (name "Net-(P8-Pad1)") (class "Default")
      (node (ref "P8") (pin "1") (pinfunction "1_1") (pintype "passive"))
      (node (ref "RL1") (pin "NO") (pinfunction "NO_NO") (pintype "passive"))
    )
    (net (code "45") (name "Net-(P8-Pad2)") (class "Default")
      (node (ref "P8") (pin "2") (pinfunction "2_2") (pintype "passive"))
      (node (ref "RL1") (pin "COM") (pinfunction "COM_COM") (pintype "passive"))
    )
    (net (code "46") (name "Net-(P9-Pad1)") (class "Default")
      (node (ref "P9") (pin "1") (pinfunction "1_1") (pintype "passive"))
      (node (ref "RL2") (pin "NO") (pinfunction "NO_NO") (pintype "passive"))
    )
    (net (code "47") (name "Net-(P9-Pad2)") (class "Default")
      (node (ref "P9") (pin "2") (pinfunction "2_2") (pintype "passive"))
      (node (ref "RL2") (pin "COM") (pinfunction "COM_COM") (pintype "passive"))
    )
    (net (code "48") (name "Net-(P10-Pad1)") (class "Default")
      (node (ref "P10") (pin "1") (pinfunction "1_1") (pintype "passive"))
      (node (ref "RL3") (pin "NO") (pinfunction "NO_NO") (pintype "passive"))
    )
    (net (code "49") (name "Net-(P10-Pad2)") (class "Default")
      (node (ref "P10") (pin "2") (pinfunction "2_2") (pintype "passive"))
      (node (ref "RL3") (pin "COM") (pinfunction "COM_COM") (pintype "passive"))
    )
    (net (code "50") (name "Net-(P11-Pad1)") (class "Default")
      (node (ref "P11") (pin "1") (pinfunction "1_1") (pintype "passive"))
      (node (ref "RL4") (pin "NO") (pinfunction "NO_NO") (pintype "passive"))
    )
    (net (code "51") (name "Net-(P11-Pad2)") (class "Default")
      (node (ref "P11") (pin "2") (pinfunction "2_2") (pintype "passive"))
      (node (ref "RL4") (pin "COM") (pinfunction "COM_COM") (pintype "passive"))
    )
    (net (code "52") (name "Net-(PWR-A)") (class "Default")
      (node (ref "PWR") (pin "2") (pinfunction "A_2") (pintype "passive"))
      (node (ref "R1") (pin "1") (pinfunction "1_1") (pintype "passive"))
    )
    (net (code "53") (name "Net-(R10-Pad2)") (class "Default")
      (node (ref "R10") (pin "2") (pinfunction "2_2") (pintype "passive"))
      (node (ref "R11") (pin "1") (pinfunction "1_1") (pintype "passive"))
    )
    (net (code "54") (name "Net-(SW4-NO1)") (class "Default")
      (node (ref "BT1") (pin "1+") (pinfunction "1+_1+") (pintype "passive"))
      (node (ref "SW4") (pin "3") (pinfunction "NO1_3") (pintype "passive"))
    )
    (net (code "55") (name "Net-(U1-VOUT)") (class "Default")
      (node (ref "R22") (pin "2") (pinfunction "2_2") (pintype "passive"))
      (node (ref "U1") (pin "3") (pinfunction "VOUT_3") (pintype "passive"))
    )
    (net (code "56") (name "Net-(U4-1Y)") (class "Default")
      (node (ref "R4") (pin "2") (pinfunction "2_2") (pintype "passive"))
      (node (ref "U4") (pin "11") (pinfunction "5A_11") (pintype "input"))
      (node (ref "U4") (pin "2") (pinfunction "1Y_2") (pintype "output"))
    )
    (net (code "57") (name "Net-(U4-2A)") (class "Default")
      (node (ref "R5") (pin "2") (pinfunction "2_2") (pintype "passive"))
      (node (ref "U4") (pin "3") (pinfunction "2A_3") (pintype "input"))
      (node (ref "U4") (pin "8") (pinfunction "4Y_8") (pintype "output"))
    )
    (net (code "58") (name "Net-(U4-6Y)") (class "Default")
      (node (ref "U4") (pin "12") (pinfunction "6Y_12") (pintype "output"))
      (node (ref "U5") (pin "2") (pinfunction "~{RE}_2") (pintype "input"))
      (node (ref "U5") (pin "3") (pinfunction "DE_3") (pintype "input"))
    )
    (net (code "59") (name "unconnected-(GDT1-Pad3)") (class "Default")
      (node (ref "GDT1") (pin "3") (pinfunction "3_3") (pintype "passive"))
    )
    (net (code "60") (name "unconnected-(H1-Pad1)") (class "Default")
      (node (ref "H1") (pin "1") (pinfunction "1_1") (pintype "passive"))
    )
    (net (code "61") (name "unconnected-(H2-Pad1)") (class "Default")
      (node (ref "H2") (pin "1") (pinfunction "1_1") (pintype "passive"))
    )
    (net (code "62") (name "unconnected-(H3-Pad1)") (class "Default")
      (node (ref "H3") (pin "1") (pinfunction "1_1") (pintype "passive"))
    )
    (net (code "63") (name "unconnected-(H4-Pad1)") (class "Default")
      (node (ref "H4") (pin "1") (pinfunction "1_1") (pintype "passive"))
    )
    (net (code "64") (name "unconnected-(RL1-PadNC)") (class "Default")
      (node (ref "RL1") (pin "NC") (pinfunction "NC_NC") (pintype "passive"))
    )
    (net (code "65") (name "unconnected-(RL2-PadNC)") (class "Default")
      (node (ref "RL2") (pin "NC") (pinfunction "NC_NC") (pintype "passive"))
    )
    (net (code "66") (name "unconnected-(RL3-PadNC)") (class "Default")
      (node (ref "RL3") (pin "NC") (pinfunction "NC_NC") (pintype "passive"))
    )
    (net (code "67") (name "unconnected-(RL4-PadNC)") (class "Default")
      (node (ref "RL4") (pin "NC") (pinfunction "NC_NC") (pintype "passive"))
    )
    (net (code "68") (name "unconnected-(SW4-NC1-Pad1)") (class "Default")
      (node (ref "SW4") (pin "1") (pinfunction "NC1_1") (pintype "passive"))
    )
    (net (code "69") (name "unconnected-(U4-3A-Pad5)") (class "Default")
      (node (ref "U4") (pin "5") (pinfunction "3A_5") (pintype "input"))
    )
    (net (code "70") (name "unconnected-(U4-3Y-Pad6)") (class "Default")
      (node (ref "U4") (pin "6") (pinfunction "3Y_6") (pintype "output"))
    )
    (net (code "71") (name "unconnected-(U6-1B-Pad1)") (class "Default")
      (node (ref "U6") (pin "1") (pinfunction "1B_1") (pintype "passive"))
    )
    (net (code "72") (name "unconnected-(U6-1C-Pad16)") (class "Default")
      (node (ref "U6") (pin "16") (pinfunction "1C_16") (pintype "passive"))
    )
    (net (code "73") (name "unconnected-(U6-2B-Pad2)") (class "Default")
      (node (ref "U6") (pin "2") (pinfunction "2B_2") (pintype "passive"))
    )
    (net (code "74") (name "unconnected-(U6-2C-Pad15)") (class "Default")
      (node (ref "U6") (pin "15") (pinfunction "2C_15") (pintype "passive"))
    )
    (net (code "75") (name "unconnected-(U6-3B-Pad3)") (class "Default")
      (node (ref "U6") (pin "3") (pinfunction "3B_3") (pintype "passive"))
    )
    (net (code "76") (name "unconnected-(U6-3C-Pad14)") (class "Default")
      (node (ref "U6") (pin "14") (pinfunction "3C_14") (pintype "passive"))
    )
    (net (code "77") (name "unconnected-(U7-IO2-Pad24)") (class "Default")
      (node (ref "U7") (pin "24") (pinfunction "IO2_24") (pintype "bidirectional"))
    )
    (net (code "78") (name "unconnected-(U7-IO13-Pad16)") (class "Default")
      (node (ref "U7") (pin "16") (pinfunction "IO13_16") (pintype "bidirectional"))
    )
    (net (code "79") (name "unconnected-(U7-IO15-Pad23)") (class "Default")
      (node (ref "U7") (pin "23") (pinfunction "IO15_23") (pintype "bidirectional"))
    )
    (net (code "80") (name "unconnected-(U7-IO22-Pad36)") (class "Default")
      (node (ref "U7") (pin "36") (pinfunction "IO22_36") (pintype "bidirectional"))
    )
    (net (code "81") (name "unconnected-(U7-IO23-Pad37)") (class "Default")
      (node (ref "U7") (pin "37") (pinfunction "IO23_37") (pintype "bidirectional"))
    )
    (net (code "82") (name "unconnected-(U7-IO34-Pad6)") (class "Default")
      (node (ref "U7") (pin "6") (pinfunction "IO34_6") (pintype "input"))
    )
    (net (code "83") (name "unconnected-(U7-IO35-Pad7)") (class "Default")
      (node (ref "U7") (pin "7") (pinfunction "IO35_7") (pintype "input"))
    )
    (net (code "84") (name "unconnected-(U7-IO36{slash}SENSOR_VP-Pad4)") (class "Default")
      (node (ref "U7") (pin "4") (pinfunction "IO36/SENSOR_VP_4") (pintype "input"))
    )
    (net (code "85") (name "unconnected-(U7-IO39{slash}SENSOR_VN-Pad5)") (class "Default")
      (node (ref "U7") (pin "5") (pinfunction "IO39/SENSOR_VN_5") (pintype "input"))
    )
    (net (code "86") (name "unconnected-(U7-NC-Pad32)") (class "Default")
      (node (ref "U7") (pin "32") (pinfunction "NC_32") (pintype "passive"))
    )
    (net (code "87") (name "unconnected-(U7-SCL{slash}CLK-Pad20)") (class "Default")
      (node (ref "U7") (pin "20") (pinfunction "SCL/CLK_20") (pintype "bidirectional"))
    )
    (net (code "88") (name "unconnected-(U7-SCS{slash}CMD-Pad19)") (class "Default")
      (node (ref "U7") (pin "19") (pinfunction "SCS/CMD_19") (pintype "bidirectional"))
    )
    (net (code "89") (name "unconnected-(U7-SD1{slash}SD1-Pad22)") (class "Default")
      (node (ref "U7") (pin "22") (pinfunction "SD1/SD1_22") (pintype "bidirectional"))
    )
    (net (code "90") (name "unconnected-(U7-SDO{slash}SD0-Pad21)") (class "Default")
      (node (ref "U7") (pin "21") (pinfunction "SDO/SD0_21") (pintype "bidirectional"))
    )
    (net (code "91") (name "unconnected-(U7-SHD{slash}SD2-Pad17)") (class "Default")
      (node (ref "U7") (pin "17") (pinfunction "SHD/SD2_17") (pintype "bidirectional"))
    )
    (net (code "92") (name "unconnected-(U7-SWP{slash}SD3-Pad18)") (class "Default")
      (node (ref "U7") (pin "18") (pinfunction "SWP/SD3_18") (pintype "bidirectional"))
    )
  )
)
